# SMHome_SDNL.net
KiCad netlist of a schematic drawn in Altium Designer
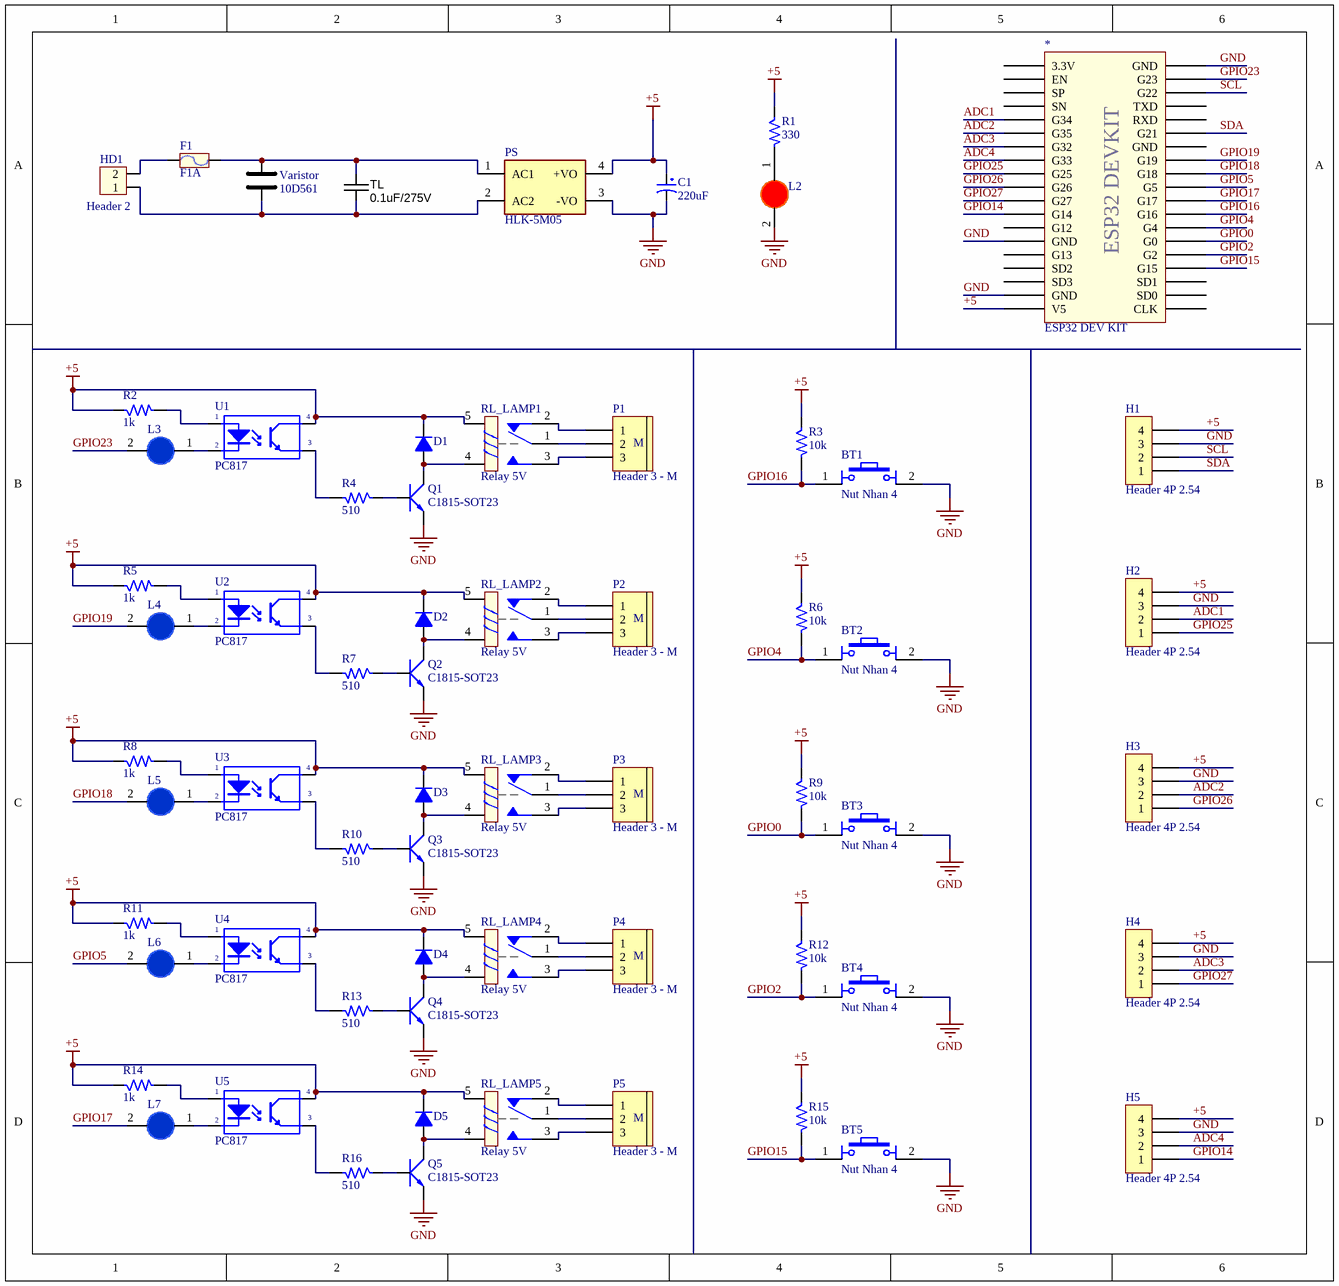
[diagram p0: SMHome_SDNL.SchDoc]

(export (version "E")
  (design (tool "Eeschema 10.0.6"))
  (components
    (comp (ref "*")
      (value "ESP32 DEV KIT")
      (footprint "ESP32 DEVKIT")
      (libsource (lib "Altium_Lib_by_KhueNguyenCreator") (part "ESP32 DEV KIT"))
    )
    (comp (ref "BT1")
      (value "Nut Nhan 4")
      (footprint "Nut Nhan 4 Chan Cam 6x6")
      (description "Nut Nhan 4 Chan 6x6mm")
      (libsource (lib "Altium_Lib_by_KhueNguyenCreator") (part "Nut Nhan 4 Chan Cam 6x6"))
    )
    (comp (ref "BT2")
      (value "Nut Nhan 4")
      (footprint "Nut Nhan 4 Chan Cam 6x6")
      (description "Nut Nhan 4 Chan 6x6mm")
      (libsource (lib "Altium_Lib_by_KhueNguyenCreator") (part "Nut Nhan 4 Chan Cam 6x6"))
    )
    (comp (ref "BT3")
      (value "Nut Nhan 4")
      (footprint "Nut Nhan 4 Chan Cam 6x6")
      (description "Nut Nhan 4 Chan 6x6mm")
      (libsource (lib "Altium_Lib_by_KhueNguyenCreator") (part "Nut Nhan 4 Chan Cam 6x6"))
    )
    (comp (ref "BT4")
      (value "Nut Nhan 4")
      (footprint "Nut Nhan 4 Chan Cam 6x6")
      (description "Nut Nhan 4 Chan 6x6mm")
      (libsource (lib "Altium_Lib_by_KhueNguyenCreator") (part "Nut Nhan 4 Chan Cam 6x6"))
    )
    (comp (ref "BT5")
      (value "Nut Nhan 4")
      (footprint "Nut Nhan 4 Chan Cam 6x6")
      (description "Nut Nhan 4 Chan 6x6mm")
      (libsource (lib "Altium_Lib_by_KhueNguyenCreator") (part "Nut Nhan 4 Chan Cam 6x6"))
    )
    (comp (ref "C1")
      (value "220uF")
      (footprint "CP1.5/3.4")
      (description "Cap 100uF/35V - 470uF/16V")
      (libsource (lib "syhaunguyen") (part "CP3"))
    )
    (comp (ref "D1")
      (value "Diode  1N4007")
      (footprint "DO-214AC")
      (description "Diode 1A")
      (libsource (lib "my Library") (part "Diode  1N4007"))
    )
    (comp (ref "D2")
      (value "Diode  1N4007")
      (footprint "DO-214AC")
      (description "Diode 1A")
      (libsource (lib "my Library") (part "Diode  1N4007"))
    )
    (comp (ref "D3")
      (value "Diode  1N4007")
      (footprint "DO-214AC")
      (description "Diode 1A")
      (libsource (lib "my Library") (part "Diode  1N4007"))
    )
    (comp (ref "D4")
      (value "Diode  1N4007")
      (footprint "DO-214AC")
      (description "Diode 1A")
      (libsource (lib "my Library") (part "Diode  1N4007"))
    )
    (comp (ref "D5")
      (value "Diode  1N4007")
      (footprint "DO-214AC")
      (description "Diode 1A")
      (libsource (lib "my Library") (part "Diode  1N4007"))
    )
    (comp (ref "F1")
      (value "F1A")
      (footprint "Fuse")
      (description "Fuse")
      (fields (field (name "DESIGNED BY") "VanDungEvn"))
      (libsource (lib "syhaunguyen") (part "Fuse"))
    )
    (comp (ref "H1")
      (value "Header 4P 2.54")
      (footprint "XH2.54M-4")
      (description "Cắm")
      (libsource (lib "Altium_Lib_by_KhueNguyenCreator") (part "Header 4P 2.54 Duc Thang"))
    )
    (comp (ref "H2")
      (value "Header 4P 2.54")
      (footprint "XH2.54M-4")
      (description "Cắm")
      (libsource (lib "Altium_Lib_by_KhueNguyenCreator") (part "Header 4P 2.54 Duc Thang"))
    )
    (comp (ref "H3")
      (value "Header 4P 2.54")
      (footprint "XH2.54M-4")
      (description "Cắm")
      (libsource (lib "Altium_Lib_by_KhueNguyenCreator") (part "Header 4P 2.54 Duc Thang"))
    )
    (comp (ref "H4")
      (value "Header 4P 2.54")
      (footprint "XH2.54M-4")
      (description "Cắm")
      (libsource (lib "Altium_Lib_by_KhueNguyenCreator") (part "Header 4P 2.54 Duc Thang"))
    )
    (comp (ref "H5")
      (value "Header 4P 2.54")
      (footprint "XH2.54M-4")
      (description "Cắm")
      (libsource (lib "Altium_Lib_by_KhueNguyenCreator") (part "Header 4P 2.54 Duc Thang"))
    )
    (comp (ref "HD1")
      (value "Header 2")
      (footprint "HED2")
      (description "Header 2 (Green)")
      (libsource (lib "My library altium") (part "Header 2"))
    )
    (comp (ref "L2")
      (value "~")
      (footprint "LED-1206-Red")
      (description "Dán")
      (libsource (lib "Altium_Lib_by_KhueNguyenCreator") (part "LED 1206 Do"))
    )
    (comp (ref "L3")
      (value "~")
      (footprint "LED-1206-Blue")
      (description "Dán")
      (libsource (lib "Altium_Lib_by_KhueNguyenCreator") (part "LED 1206 Xanh Duong"))
    )
    (comp (ref "L4")
      (value "~")
      (footprint "LED-1206-Blue")
      (description "Dán")
      (libsource (lib "Altium_Lib_by_KhueNguyenCreator") (part "LED 1206 Xanh Duong"))
    )
    (comp (ref "L5")
      (value "~")
      (footprint "LED-1206-Blue")
      (description "Dán")
      (libsource (lib "Altium_Lib_by_KhueNguyenCreator") (part "LED 1206 Xanh Duong"))
    )
    (comp (ref "L6")
      (value "~")
      (footprint "LED-1206-Blue")
      (description "Dán")
      (libsource (lib "Altium_Lib_by_KhueNguyenCreator") (part "LED 1206 Xanh Duong"))
    )
    (comp (ref "L7")
      (value "~")
      (footprint "LED-1206-Blue")
      (description "Dán")
      (libsource (lib "Altium_Lib_by_KhueNguyenCreator") (part "LED 1206 Xanh Duong"))
    )
    (comp (ref "P1")
      (value "Header 3 - M")
      (footprint "Medium - Header 3")
      (description "Header, 3-Pin, Medium")
      (fields (field (name "PUBLISHER") "Altium Limited"))
      (libsource (lib "NBBLib 14-03-2012") (part "Header 3 - M"))
    )
    (comp (ref "P2")
      (value "Header 3 - M")
      (footprint "Medium - Header 3")
      (description "Header, 3-Pin, Medium")
      (fields (field (name "PUBLISHER") "Altium Limited"))
      (libsource (lib "NBBLib 14-03-2012") (part "Header 3 - M"))
    )
    (comp (ref "P3")
      (value "Header 3 - M")
      (footprint "Medium - Header 3")
      (description "Header, 3-Pin, Medium")
      (fields (field (name "PUBLISHER") "Altium Limited"))
      (libsource (lib "NBBLib 14-03-2012") (part "Header 3 - M"))
    )
    (comp (ref "P4")
      (value "Header 3 - M")
      (footprint "Medium - Header 3")
      (description "Header, 3-Pin, Medium")
      (fields (field (name "PUBLISHER") "Altium Limited"))
      (libsource (lib "NBBLib 14-03-2012") (part "Header 3 - M"))
    )
    (comp (ref "P5")
      (value "Header 3 - M")
      (footprint "Medium - Header 3")
      (description "Header, 3-Pin, Medium")
      (fields (field (name "PUBLISHER") "Altium Limited"))
      (libsource (lib "NBBLib 14-03-2012") (part "Header 3 - M"))
    )
    (comp (ref "PS")
      (value "HLK-5M05")
      (footprint "Nguon HI-LINK 5M05")
      (description "AC DC 220V to 5V 5W 5Watt Isolated Switching Step-Down Power Supply Module Converter")
      (fields (field (name "MF") "Hi-link"))
      (libsource (lib "Altium_Lib_by_KhueNguyenCreator") (part "Nguon Hi-Link HLK-5M05"))
    )
    (comp (ref "Q1")
      (value "C1815-SOT23")
      (footprint "SOT-23")
      (description "SOT-23")
      (libsource (lib "Altium_Lib_by_KhueNguyenCreator") (part "Trans C1815 HF SMD"))
    )
    (comp (ref "Q2")
      (value "C1815-SOT23")
      (footprint "SOT-23")
      (description "SOT-23")
      (libsource (lib "Altium_Lib_by_KhueNguyenCreator") (part "Trans C1815 HF SMD"))
    )
    (comp (ref "Q3")
      (value "C1815-SOT23")
      (footprint "SOT-23")
      (description "SOT-23")
      (libsource (lib "Altium_Lib_by_KhueNguyenCreator") (part "Trans C1815 HF SMD"))
    )
    (comp (ref "Q4")
      (value "C1815-SOT23")
      (footprint "SOT-23")
      (description "SOT-23")
      (libsource (lib "Altium_Lib_by_KhueNguyenCreator") (part "Trans C1815 HF SMD"))
    )
    (comp (ref "Q5")
      (value "C1815-SOT23")
      (footprint "SOT-23")
      (description "SOT-23")
      (libsource (lib "Altium_Lib_by_KhueNguyenCreator") (part "Trans C1815 HF SMD"))
    )
    (comp (ref "R1")
      (value "330")
      (footprint "SM-RES-1206")
      (description "Resistor 1/4W")
      (libsource (lib "syhaunguyen") (part "R"))
    )
    (comp (ref "R2")
      (value "1k")
      (footprint "SM-RES-1206")
      (description "Resistor 1/4W")
      (libsource (lib "syhaunguyen") (part "R"))
    )
    (comp (ref "R3")
      (value "10k")
      (footprint "SM-RES-1206")
      (description "Resistor 1/4W")
      (libsource (lib "syhaunguyen") (part "R"))
    )
    (comp (ref "R4")
      (value "510")
      (footprint "SM-RES-1206")
      (description "Resistor 1/4W")
      (libsource (lib "syhaunguyen") (part "R"))
    )
    (comp (ref "R5")
      (value "1k")
      (footprint "SM-RES-1206")
      (description "Resistor 1/4W")
      (libsource (lib "syhaunguyen") (part "R"))
    )
    (comp (ref "R6")
      (value "10k")
      (footprint "SM-RES-1206")
      (description "Resistor 1/4W")
      (libsource (lib "syhaunguyen") (part "R"))
    )
    (comp (ref "R7")
      (value "510")
      (footprint "SM-RES-1206")
      (description "Resistor 1/4W")
      (libsource (lib "syhaunguyen") (part "R"))
    )
    (comp (ref "R8")
      (value "1k")
      (footprint "SM-RES-1206")
      (description "Resistor 1/4W")
      (libsource (lib "syhaunguyen") (part "R"))
    )
    (comp (ref "R9")
      (value "10k")
      (footprint "SM-RES-1206")
      (description "Resistor 1/4W")
      (libsource (lib "syhaunguyen") (part "R"))
    )
    (comp (ref "R10")
      (value "510")
      (footprint "SM-RES-1206")
      (description "Resistor 1/4W")
      (libsource (lib "syhaunguyen") (part "R"))
    )
    (comp (ref "R11")
      (value "1k")
      (footprint "SM-RES-1206")
      (description "Resistor 1/4W")
      (libsource (lib "syhaunguyen") (part "R"))
    )
    (comp (ref "R12")
      (value "10k")
      (footprint "SM-RES-1206")
      (description "Resistor 1/4W")
      (libsource (lib "syhaunguyen") (part "R"))
    )
    (comp (ref "R13")
      (value "510")
      (footprint "SM-RES-1206")
      (description "Resistor 1/4W")
      (libsource (lib "syhaunguyen") (part "R"))
    )
    (comp (ref "R14")
      (value "1k")
      (footprint "SM-RES-1206")
      (description "Resistor 1/4W")
      (libsource (lib "syhaunguyen") (part "R"))
    )
    (comp (ref "R15")
      (value "10k")
      (footprint "SM-RES-1206")
      (description "Resistor 1/4W")
      (libsource (lib "syhaunguyen") (part "R"))
    )
    (comp (ref "R16")
      (value "510")
      (footprint "SM-RES-1206")
      (description "Resistor 1/4W")
      (libsource (lib "syhaunguyen") (part "R"))
    )
    (comp (ref "RL_LAMP1")
      (value "Relay 5V")
      (footprint "RL_SPDT_10A")
      (description "Relay SPDT,10A - 12VDC 5 Pin")
      (libsource (lib "syhaunguyen") (part "Relay 1"))
    )
    (comp (ref "RL_LAMP2")
      (value "Relay 5V")
      (footprint "RL_SPDT_10A")
      (description "Relay SPDT,10A - 12VDC 5 Pin")
      (libsource (lib "syhaunguyen") (part "Relay 1"))
    )
    (comp (ref "RL_LAMP3")
      (value "Relay 5V")
      (footprint "RL_SPDT_10A")
      (description "Relay SPDT,10A - 12VDC 5 Pin")
      (libsource (lib "syhaunguyen") (part "Relay 1"))
    )
    (comp (ref "RL_LAMP4")
      (value "Relay 5V")
      (footprint "RL_SPDT_10A")
      (description "Relay SPDT,10A - 12VDC 5 Pin")
      (libsource (lib "syhaunguyen") (part "Relay 1"))
    )
    (comp (ref "RL_LAMP5")
      (value "Relay 5V")
      (footprint "RL_SPDT_10A")
      (description "Relay SPDT,10A - 12VDC 5 Pin")
      (libsource (lib "syhaunguyen") (part "Relay 1"))
    )
    (comp (ref "TL")
      (value "0.1uF/275V")
      (footprint "CAPM50P720300X650_VERT")
      (description "Capacitor THD Metallized PET Film 330nF 10% 63VDC")
      (fields (field (name "TOLERANCE") "±10%"))
      (libsource (lib "My library altium") (part "CAPMF_330n_TH_MPET_63VDC_10%"))
    )
    (comp (ref "U1")
      (value "PC817")
      (footprint "DIP4/W0.3")
      (description "Single Opto")
      (libsource (lib "syhaunguyen") (part "PC817"))
    )
    (comp (ref "U2")
      (value "PC817")
      (footprint "DIP4/W0.3")
      (description "Single Opto")
      (libsource (lib "syhaunguyen") (part "PC817"))
    )
    (comp (ref "U3")
      (value "PC817")
      (footprint "DIP4/W0.3")
      (description "Single Opto")
      (libsource (lib "syhaunguyen") (part "PC817"))
    )
    (comp (ref "U4")
      (value "PC817")
      (footprint "DIP4/W0.3")
      (description "Single Opto")
      (libsource (lib "syhaunguyen") (part "PC817"))
    )
    (comp (ref "U5")
      (value "PC817")
      (footprint "DIP4/W0.3")
      (description "Single Opto")
      (libsource (lib "syhaunguyen") (part "PC817"))
    )
    (comp (ref "Varistor")
      (value "10D561")
      (footprint "103/2KV")
      (libsource (lib "My library altium") (part "103/2KV"))
    )
  )
  (nets
    (net (code "1") (name "+5") (class "Default")
      (node (ref "*") (pin "19") (pinfunction "V5_19") (pintype "passive"))
      (node (ref "C1") (pin "1") (pinfunction "1_1") (pintype "passive"))
      (node (ref "D1") (pin "K") (pinfunction "K_K") (pintype "passive"))
      (node (ref "D2") (pin "K") (pinfunction "K_K") (pintype "passive"))
      (node (ref "D3") (pin "K") (pinfunction "K_K") (pintype "passive"))
      (node (ref "D4") (pin "K") (pinfunction "K_K") (pintype "passive"))
      (node (ref "D5") (pin "K") (pinfunction "K_K") (pintype "passive"))
      (node (ref "H1") (pin "4") (pinfunction "4_4") (pintype "passive"))
      (node (ref "H2") (pin "4") (pinfunction "4_4") (pintype "passive"))
      (node (ref "H3") (pin "4") (pinfunction "4_4") (pintype "passive"))
      (node (ref "H4") (pin "4") (pinfunction "4_4") (pintype "passive"))
      (node (ref "H5") (pin "4") (pinfunction "4_4") (pintype "passive"))
      (node (ref "PS") (pin "4") (pinfunction "+VO_4") (pintype "passive"))
      (node (ref "R1") (pin "1") (pinfunction "1_1") (pintype "passive"))
      (node (ref "R11") (pin "1") (pinfunction "1_1") (pintype "passive"))
      (node (ref "R12") (pin "1") (pinfunction "1_1") (pintype "passive"))
      (node (ref "R14") (pin "1") (pinfunction "1_1") (pintype "passive"))
      (node (ref "R15") (pin "1") (pinfunction "1_1") (pintype "passive"))
      (node (ref "R2") (pin "1") (pinfunction "1_1") (pintype "passive"))
      (node (ref "R3") (pin "1") (pinfunction "1_1") (pintype "passive"))
      (node (ref "R5") (pin "1") (pinfunction "1_1") (pintype "passive"))
      (node (ref "R6") (pin "1") (pinfunction "1_1") (pintype "passive"))
      (node (ref "R8") (pin "1") (pinfunction "1_1") (pintype "passive"))
      (node (ref "R9") (pin "1") (pinfunction "1_1") (pintype "passive"))
      (node (ref "RL_LAMP1") (pin "5") (pinfunction "5_5") (pintype "passive"))
      (node (ref "RL_LAMP2") (pin "5") (pinfunction "5_5") (pintype "passive"))
      (node (ref "RL_LAMP3") (pin "5") (pinfunction "5_5") (pintype "passive"))
      (node (ref "RL_LAMP4") (pin "5") (pinfunction "5_5") (pintype "passive"))
      (node (ref "RL_LAMP5") (pin "5") (pinfunction "5_5") (pintype "passive"))
      (node (ref "U1") (pin "4") (pinfunction "C_4") (pintype "passive"))
      (node (ref "U2") (pin "4") (pinfunction "C_4") (pintype "passive"))
      (node (ref "U3") (pin "4") (pinfunction "C_4") (pintype "passive"))
      (node (ref "U4") (pin "4") (pinfunction "C_4") (pintype "passive"))
      (node (ref "U5") (pin "4") (pinfunction "C_4") (pintype "passive"))
    )
    (net (code "2") (name "/ADC1") (class "Default")
      (node (ref "*") (pin "5") (pinfunction "G34_5") (pintype "passive"))
      (node (ref "H2") (pin "2") (pinfunction "2_2") (pintype "passive"))
    )
    (net (code "3") (name "/ADC2") (class "Default")
      (node (ref "*") (pin "6") (pinfunction "G35_6") (pintype "passive"))
      (node (ref "H3") (pin "2") (pinfunction "2_2") (pintype "passive"))
    )
    (net (code "4") (name "/ADC3") (class "Default")
      (node (ref "*") (pin "7") (pinfunction "G32_7") (pintype "passive"))
      (node (ref "H4") (pin "2") (pinfunction "2_2") (pintype "passive"))
    )
    (net (code "5") (name "/ADC4") (class "Default")
      (node (ref "*") (pin "8") (pinfunction "G33_8") (pintype "passive"))
      (node (ref "H5") (pin "2") (pinfunction "2_2") (pintype "passive"))
    )
    (net (code "6") (name "/GPIO0") (class "Default")
      (node (ref "*") (pin "25") (pinfunction "G0_25") (pintype "passive"))
      (node (ref "BT3") (pin "1") (pintype "passive"))
      (node (ref "R9") (pin "2") (pinfunction "2_2") (pintype "passive"))
    )
    (net (code "7") (name "/GPIO2") (class "Default")
      (node (ref "*") (pin "24") (pinfunction "G2_24") (pintype "passive"))
      (node (ref "BT4") (pin "1") (pintype "passive"))
      (node (ref "R12") (pin "2") (pinfunction "2_2") (pintype "passive"))
    )
    (net (code "8") (name "/GPIO4") (class "Default")
      (node (ref "*") (pin "26") (pinfunction "G4_26") (pintype "passive"))
      (node (ref "BT2") (pin "1") (pintype "passive"))
      (node (ref "R6") (pin "2") (pinfunction "2_2") (pintype "passive"))
    )
    (net (code "9") (name "/GPIO5") (class "Default")
      (node (ref "*") (pin "29") (pinfunction "G5_29") (pintype "passive"))
      (node (ref "L6") (pin "2") (pinfunction "K_2") (pintype "passive"))
    )
    (net (code "10") (name "/GPIO14") (class "Default")
      (node (ref "*") (pin "12") (pinfunction "G14_12") (pintype "passive"))
      (node (ref "H5") (pin "1") (pinfunction "1_1") (pintype "passive"))
    )
    (net (code "11") (name "/GPIO15") (class "Default")
      (node (ref "*") (pin "23") (pinfunction "G15_23") (pintype "passive"))
      (node (ref "BT5") (pin "1") (pintype "passive"))
      (node (ref "R15") (pin "2") (pinfunction "2_2") (pintype "passive"))
    )
    (net (code "12") (name "/GPIO16") (class "Default")
      (node (ref "*") (pin "27") (pinfunction "G16_27") (pintype "passive"))
      (node (ref "BT1") (pin "1") (pintype "passive"))
      (node (ref "R3") (pin "2") (pinfunction "2_2") (pintype "passive"))
    )
    (net (code "13") (name "/GPIO17") (class "Default")
      (node (ref "*") (pin "28") (pinfunction "G17_28") (pintype "passive"))
      (node (ref "L7") (pin "2") (pinfunction "K_2") (pintype "passive"))
    )
    (net (code "14") (name "/GPIO18") (class "Default")
      (node (ref "*") (pin "30") (pinfunction "G18_30") (pintype "passive"))
      (node (ref "L5") (pin "2") (pinfunction "K_2") (pintype "passive"))
    )
    (net (code "15") (name "/GPIO19") (class "Default")
      (node (ref "*") (pin "31") (pinfunction "G19_31") (pintype "passive"))
      (node (ref "L4") (pin "2") (pinfunction "K_2") (pintype "passive"))
    )
    (net (code "16") (name "/GPIO23") (class "Default")
      (node (ref "*") (pin "37") (pinfunction "G23_37") (pintype "passive"))
      (node (ref "L3") (pin "2") (pinfunction "K_2") (pintype "passive"))
    )
    (net (code "17") (name "/GPIO25") (class "Default")
      (node (ref "*") (pin "9") (pinfunction "G25_9") (pintype "passive"))
      (node (ref "H2") (pin "1") (pinfunction "1_1") (pintype "passive"))
    )
    (net (code "18") (name "/GPIO26") (class "Default")
      (node (ref "*") (pin "10") (pinfunction "G26_10") (pintype "passive"))
      (node (ref "H3") (pin "1") (pinfunction "1_1") (pintype "passive"))
    )
    (net (code "19") (name "/GPIO27") (class "Default")
      (node (ref "*") (pin "11") (pinfunction "G27_11") (pintype "passive"))
      (node (ref "H4") (pin "1") (pinfunction "1_1") (pintype "passive"))
    )
    (net (code "20") (name "/SCL") (class "Default")
      (node (ref "*") (pin "36") (pinfunction "G22_36") (pintype "passive"))
      (node (ref "H1") (pin "2") (pinfunction "2_2") (pintype "passive"))
    )
    (net (code "21") (name "/SDA") (class "Default")
      (node (ref "*") (pin "33") (pinfunction "G21_33") (pintype "passive"))
      (node (ref "H1") (pin "1") (pinfunction "1_1") (pintype "passive"))
    )
    (net (code "22") (name "GND") (class "Default")
      (node (ref "*") (pin "14") (pinfunction "GND_14") (pintype "passive"))
      (node (ref "*") (pin "18") (pinfunction "GND_18") (pintype "passive"))
      (node (ref "*") (pin "38") (pinfunction "GND_38") (pintype "passive"))
      (node (ref "BT1") (pin "2") (pintype "passive"))
      (node (ref "BT2") (pin "2") (pintype "passive"))
      (node (ref "BT3") (pin "2") (pintype "passive"))
      (node (ref "BT4") (pin "2") (pintype "passive"))
      (node (ref "BT5") (pin "2") (pintype "passive"))
      (node (ref "C1") (pin "2") (pinfunction "2_2") (pintype "passive"))
      (node (ref "H1") (pin "3") (pinfunction "3_3") (pintype "passive"))
      (node (ref "H2") (pin "3") (pinfunction "3_3") (pintype "passive"))
      (node (ref "H3") (pin "3") (pinfunction "3_3") (pintype "passive"))
      (node (ref "H4") (pin "3") (pinfunction "3_3") (pintype "passive"))
      (node (ref "H5") (pin "3") (pinfunction "3_3") (pintype "passive"))
      (node (ref "L2") (pin "2") (pinfunction "K_2") (pintype "passive"))
      (node (ref "PS") (pin "3") (pinfunction "-VO_3") (pintype "passive"))
      (node (ref "Q1") (pin "2") (pinfunction "E_2") (pintype "passive"))
      (node (ref "Q2") (pin "2") (pinfunction "E_2") (pintype "passive"))
      (node (ref "Q3") (pin "2") (pinfunction "E_2") (pintype "passive"))
      (node (ref "Q4") (pin "2") (pinfunction "E_2") (pintype "passive"))
      (node (ref "Q5") (pin "2") (pinfunction "E_2") (pintype "passive"))
    )
    (net (code "23") (name "Net-(F1-Pad1)") (class "Default")
      (node (ref "F1") (pin "1") (pinfunction "1_1") (pintype "passive"))
      (node (ref "HD1") (pin "2") (pinfunction "2_2") (pintype "passive"))
    )
    (net (code "24") (name "Net-(L2-A)") (class "Default")
      (node (ref "L2") (pin "1") (pinfunction "A_1") (pintype "passive"))
      (node (ref "R1") (pin "2") (pinfunction "2_2") (pintype "passive"))
    )
    (net (code "25") (name "Net-(L3-A)") (class "Default")
      (node (ref "L3") (pin "1") (pinfunction "A_1") (pintype "passive"))
      (node (ref "U1") (pin "2") (pinfunction "K_2") (pintype "passive"))
    )
    (net (code "26") (name "Net-(L4-A)") (class "Default")
      (node (ref "L4") (pin "1") (pinfunction "A_1") (pintype "passive"))
      (node (ref "U2") (pin "2") (pinfunction "K_2") (pintype "passive"))
    )
    (net (code "27") (name "Net-(L5-A)") (class "Default")
      (node (ref "L5") (pin "1") (pinfunction "A_1") (pintype "passive"))
      (node (ref "U3") (pin "2") (pinfunction "K_2") (pintype "passive"))
    )
    (net (code "28") (name "Net-(L6-A)") (class "Default")
      (node (ref "L6") (pin "1") (pinfunction "A_1") (pintype "passive"))
      (node (ref "U4") (pin "2") (pinfunction "K_2") (pintype "passive"))
    )
    (net (code "29") (name "Net-(L7-A)") (class "Default")
      (node (ref "L7") (pin "1") (pinfunction "A_1") (pintype "passive"))
      (node (ref "U5") (pin "2") (pinfunction "K_2") (pintype "passive"))
    )
    (net (code "30") (name "Net-(P1-Pad1)") (class "Default")
      (node (ref "P1") (pin "1") (pinfunction "1_1") (pintype "passive"))
      (node (ref "RL_LAMP1") (pin "2") (pinfunction "2_2") (pintype "passive"))
    )
    (net (code "31") (name "Net-(P1-Pad2)") (class "Default")
      (node (ref "P1") (pin "2") (pinfunction "2_2") (pintype "passive"))
      (node (ref "RL_LAMP1") (pin "1") (pinfunction "1_1") (pintype "passive"))
    )
    (net (code "32") (name "Net-(P1-Pad3)") (class "Default")
      (node (ref "P1") (pin "3") (pinfunction "3_3") (pintype "passive"))
      (node (ref "RL_LAMP1") (pin "3") (pinfunction "3_3") (pintype "passive"))
    )
    (net (code "33") (name "Net-(P2-Pad1)") (class "Default")
      (node (ref "P2") (pin "1") (pinfunction "1_1") (pintype "passive"))
      (node (ref "RL_LAMP2") (pin "2") (pinfunction "2_2") (pintype "passive"))
    )
    (net (code "34") (name "Net-(P2-Pad2)") (class "Default")
      (node (ref "P2") (pin "2") (pinfunction "2_2") (pintype "passive"))
      (node (ref "RL_LAMP2") (pin "1") (pinfunction "1_1") (pintype "passive"))
    )
    (net (code "35") (name "Net-(P2-Pad3)") (class "Default")
      (node (ref "P2") (pin "3") (pinfunction "3_3") (pintype "passive"))
      (node (ref "RL_LAMP2") (pin "3") (pinfunction "3_3") (pintype "passive"))
    )
    (net (code "36") (name "Net-(P3-Pad1)") (class "Default")
      (node (ref "P3") (pin "1") (pinfunction "1_1") (pintype "passive"))
      (node (ref "RL_LAMP3") (pin "2") (pinfunction "2_2") (pintype "passive"))
    )
    (net (code "37") (name "Net-(P3-Pad2)") (class "Default")
      (node (ref "P3") (pin "2") (pinfunction "2_2") (pintype "passive"))
      (node (ref "RL_LAMP3") (pin "1") (pinfunction "1_1") (pintype "passive"))
    )
    (net (code "38") (name "Net-(P3-Pad3)") (class "Default")
      (node (ref "P3") (pin "3") (pinfunction "3_3") (pintype "passive"))
      (node (ref "RL_LAMP3") (pin "3") (pinfunction "3_3") (pintype "passive"))
    )
    (net (code "39") (name "Net-(P4-Pad1)") (class "Default")
      (node (ref "P4") (pin "1") (pinfunction "1_1") (pintype "passive"))
      (node (ref "RL_LAMP4") (pin "2") (pinfunction "2_2") (pintype "passive"))
    )
    (net (code "40") (name "Net-(P4-Pad2)") (class "Default")
      (node (ref "P4") (pin "2") (pinfunction "2_2") (pintype "passive"))
      (node (ref "RL_LAMP4") (pin "1") (pinfunction "1_1") (pintype "passive"))
    )
    (net (code "41") (name "Net-(P4-Pad3)") (class "Default")
      (node (ref "P4") (pin "3") (pinfunction "3_3") (pintype "passive"))
      (node (ref "RL_LAMP4") (pin "3") (pinfunction "3_3") (pintype "passive"))
    )
    (net (code "42") (name "Net-(P5-Pad1)") (class "Default")
      (node (ref "P5") (pin "1") (pinfunction "1_1") (pintype "passive"))
      (node (ref "RL_LAMP5") (pin "2") (pinfunction "2_2") (pintype "passive"))
    )
    (net (code "43") (name "Net-(P5-Pad2)") (class "Default")
      (node (ref "P5") (pin "2") (pinfunction "2_2") (pintype "passive"))
      (node (ref "RL_LAMP5") (pin "1") (pinfunction "1_1") (pintype "passive"))
    )
    (net (code "44") (name "Net-(P5-Pad3)") (class "Default")
      (node (ref "P5") (pin "3") (pinfunction "3_3") (pintype "passive"))
      (node (ref "RL_LAMP5") (pin "3") (pinfunction "3_3") (pintype "passive"))
    )
    (net (code "45") (name "Net-(PS-AC1)") (class "Default")
      (node (ref "F1") (pin "2") (pinfunction "2_2") (pintype "passive"))
      (node (ref "PS") (pin "1") (pinfunction "AC1_1") (pintype "passive"))
      (node (ref "TL") (pin "1") (pintype "passive"))
      (node (ref "Varistor") (pin "2") (pinfunction "2_2") (pintype "passive"))
    )
    (net (code "46") (name "Net-(PS-AC2)") (class "Default")
      (node (ref "HD1") (pin "1") (pinfunction "1_1") (pintype "passive"))
      (node (ref "PS") (pin "2") (pinfunction "AC2_2") (pintype "passive"))
      (node (ref "TL") (pin "2") (pintype "passive"))
      (node (ref "Varistor") (pin "1") (pinfunction "1_1") (pintype "passive"))
    )
    (net (code "47") (name "Net-(Q1-B)") (class "Default")
      (node (ref "Q1") (pin "1") (pinfunction "B_1") (pintype "passive"))
      (node (ref "R4") (pin "1") (pinfunction "1_1") (pintype "passive"))
    )
    (net (code "48") (name "Net-(Q1-C)") (class "Default")
      (node (ref "D1") (pin "A") (pinfunction "A_A") (pintype "passive"))
      (node (ref "Q1") (pin "3") (pinfunction "C_3") (pintype "passive"))
      (node (ref "RL_LAMP1") (pin "4") (pinfunction "4_4") (pintype "passive"))
    )
    (net (code "49") (name "Net-(Q2-B)") (class "Default")
      (node (ref "Q2") (pin "1") (pinfunction "B_1") (pintype "passive"))
      (node (ref "R7") (pin "1") (pinfunction "1_1") (pintype "passive"))
    )
    (net (code "50") (name "Net-(Q2-C)") (class "Default")
      (node (ref "D2") (pin "A") (pinfunction "A_A") (pintype "passive"))
      (node (ref "Q2") (pin "3") (pinfunction "C_3") (pintype "passive"))
      (node (ref "RL_LAMP2") (pin "4") (pinfunction "4_4") (pintype "passive"))
    )
    (net (code "51") (name "Net-(Q3-B)") (class "Default")
      (node (ref "Q3") (pin "1") (pinfunction "B_1") (pintype "passive"))
      (node (ref "R10") (pin "1") (pinfunction "1_1") (pintype "passive"))
    )
    (net (code "52") (name "Net-(Q3-C)") (class "Default")
      (node (ref "D3") (pin "A") (pinfunction "A_A") (pintype "passive"))
      (node (ref "Q3") (pin "3") (pinfunction "C_3") (pintype "passive"))
      (node (ref "RL_LAMP3") (pin "4") (pinfunction "4_4") (pintype "passive"))
    )
    (net (code "53") (name "Net-(Q4-B)") (class "Default")
      (node (ref "Q4") (pin "1") (pinfunction "B_1") (pintype "passive"))
      (node (ref "R13") (pin "1") (pinfunction "1_1") (pintype "passive"))
    )
    (net (code "54") (name "Net-(Q4-C)") (class "Default")
      (node (ref "D4") (pin "A") (pinfunction "A_A") (pintype "passive"))
      (node (ref "Q4") (pin "3") (pinfunction "C_3") (pintype "passive"))
      (node (ref "RL_LAMP4") (pin "4") (pinfunction "4_4") (pintype "passive"))
    )
    (net (code "55") (name "Net-(Q5-B)") (class "Default")
      (node (ref "Q5") (pin "1") (pinfunction "B_1") (pintype "passive"))
      (node (ref "R16") (pin "1") (pinfunction "1_1") (pintype "passive"))
    )
    (net (code "56") (name "Net-(Q5-C)") (class "Default")
      (node (ref "D5") (pin "A") (pinfunction "A_A") (pintype "passive"))
      (node (ref "Q5") (pin "3") (pinfunction "C_3") (pintype "passive"))
      (node (ref "RL_LAMP5") (pin "4") (pinfunction "4_4") (pintype "passive"))
    )
    (net (code "57") (name "Net-(U1-A)") (class "Default")
      (node (ref "R2") (pin "2") (pinfunction "2_2") (pintype "passive"))
      (node (ref "U1") (pin "1") (pinfunction "A_1") (pintype "passive"))
    )
    (net (code "58") (name "Net-(U1-E)") (class "Default")
      (node (ref "R4") (pin "2") (pinfunction "2_2") (pintype "passive"))
      (node (ref "U1") (pin "3") (pinfunction "E_3") (pintype "passive"))
    )
    (net (code "59") (name "Net-(U2-A)") (class "Default")
      (node (ref "R5") (pin "2") (pinfunction "2_2") (pintype "passive"))
      (node (ref "U2") (pin "1") (pinfunction "A_1") (pintype "passive"))
    )
    (net (code "60") (name "Net-(U2-E)") (class "Default")
      (node (ref "R7") (pin "2") (pinfunction "2_2") (pintype "passive"))
      (node (ref "U2") (pin "3") (pinfunction "E_3") (pintype "passive"))
    )
    (net (code "61") (name "Net-(U3-A)") (class "Default")
      (node (ref "R8") (pin "2") (pinfunction "2_2") (pintype "passive"))
      (node (ref "U3") (pin "1") (pinfunction "A_1") (pintype "passive"))
    )
    (net (code "62") (name "Net-(U3-E)") (class "Default")
      (node (ref "R10") (pin "2") (pinfunction "2_2") (pintype "passive"))
      (node (ref "U3") (pin "3") (pinfunction "E_3") (pintype "passive"))
    )
    (net (code "63") (name "Net-(U4-A)") (class "Default")
      (node (ref "R11") (pin "2") (pinfunction "2_2") (pintype "passive"))
      (node (ref "U4") (pin "1") (pinfunction "A_1") (pintype "passive"))
    )
    (net (code "64") (name "Net-(U4-E)") (class "Default")
      (node (ref "R13") (pin "2") (pinfunction "2_2") (pintype "passive"))
      (node (ref "U4") (pin "3") (pinfunction "E_3") (pintype "passive"))
    )
    (net (code "65") (name "Net-(U5-A)") (class "Default")
      (node (ref "R14") (pin "2") (pinfunction "2_2") (pintype "passive"))
      (node (ref "U5") (pin "1") (pinfunction "A_1") (pintype "passive"))
    )
    (net (code "66") (name "Net-(U5-E)") (class "Default")
      (node (ref "R16") (pin "2") (pinfunction "2_2") (pintype "passive"))
      (node (ref "U5") (pin "3") (pinfunction "E_3") (pintype "passive"))
    )
    (net (code "67") (name "unconnected-(*-3.3V-Pad1)") (class "Default")
      (node (ref "*") (pin "1") (pinfunction "3.3V_1") (pintype "passive"))
    )
    (net (code "68") (name "unconnected-(*-CLK-Pad20)") (class "Default")
      (node (ref "*") (pin "20") (pinfunction "CLK_20") (pintype "passive"))
    )
    (net (code "69") (name "unconnected-(*-EN-Pad2)") (class "Default")
      (node (ref "*") (pin "2") (pinfunction "EN_2") (pintype "passive"))
    )
    (net (code "70") (name "unconnected-(*-G12-Pad13)") (class "Default")
      (node (ref "*") (pin "13") (pinfunction "G12_13") (pintype "passive"))
    )
    (net (code "71") (name "unconnected-(*-G13-Pad15)") (class "Default")
      (node (ref "*") (pin "15") (pinfunction "G13_15") (pintype "passive"))
    )
    (net (code "72") (name "unconnected-(*-GND-Pad32)") (class "Default")
      (node (ref "*") (pin "32") (pinfunction "GND_32") (pintype "passive"))
    )
    (net (code "73") (name "unconnected-(*-RXD-Pad34)") (class "Default")
      (node (ref "*") (pin "34") (pinfunction "RXD_34") (pintype "passive"))
    )
    (net (code "74") (name "unconnected-(*-SD0-Pad21)") (class "Default")
      (node (ref "*") (pin "21") (pinfunction "SD0_21") (pintype "passive"))
    )
    (net (code "75") (name "unconnected-(*-SD1-Pad22)") (class "Default")
      (node (ref "*") (pin "22") (pinfunction "SD1_22") (pintype "passive"))
    )
    (net (code "76") (name "unconnected-(*-SD2-Pad16)") (class "Default")
      (node (ref "*") (pin "16") (pinfunction "SD2_16") (pintype "passive"))
    )
    (net (code "77") (name "unconnected-(*-SD3-Pad17)") (class "Default")
      (node (ref "*") (pin "17") (pinfunction "SD3_17") (pintype "passive"))
    )
    (net (code "78") (name "unconnected-(*-SN-Pad4)") (class "Default")
      (node (ref "*") (pin "4") (pinfunction "SN_4") (pintype "passive"))
    )
    (net (code "79") (name "unconnected-(*-SP-Pad3)") (class "Default")
      (node (ref "*") (pin "3") (pinfunction "SP_3") (pintype "passive"))
    )
    (net (code "80") (name "unconnected-(*-TXD-Pad35)") (class "Default")
      (node (ref "*") (pin "35") (pinfunction "TXD_35") (pintype "passive"))
    )
  )
)
